# BG_IO_Schematic.net
KiCad netlist of a schematic drawn in Altium Designer
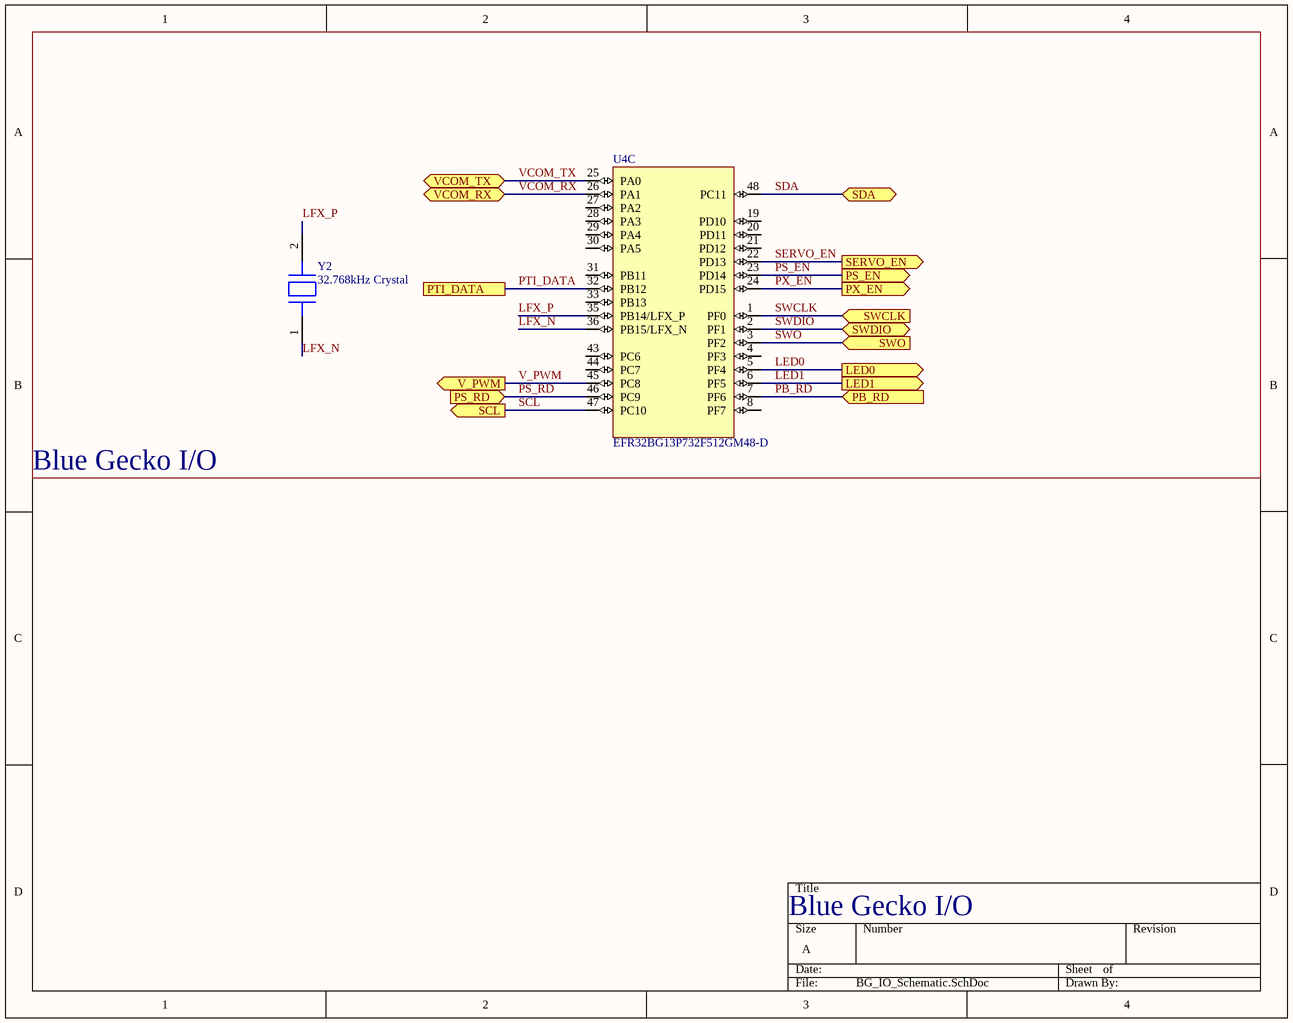
[diagram p0: BG_IO_Schematic.SchDoc]

(export (version "E")
  (design (tool "Eeschema 10.0.6"))
  (components
    (comp (ref "U4")
      (value "EFR32BG13P732F512GM48-D")
      (footprint "48-QFN_7x7")
      (description "Blue Gecko QFN48 2.4 G 19 dB BLE/Proprietary 512 kB 64 kB(RAM) 31GPIO")
      (fields (field (name "MANUFACTURER") "Silicon Labs"))
      (libsource (lib "PartsLib") (part "EFR32BG13P732F512GM48-D"))
    )
    (comp (ref "Y2")
      (value "32.768kHz Crystal")
      (footprint "DFN153P160X50-2N")
      (description "CRYSTAL 32.768KHZ 7PF SMD")
      (fields
        (field (name "MANUFACTURER") "Abracon")
        (field (name "MANUFACTURER PART NUMBER") "ABS05-32.768KHZ-7-T")
      )
      (libsource (lib "PartsLib") (part "ABS05-32.768KHZ-7-T"))
    )
  )
  (nets
    (net (code "1") (name "/LED0") (class "Default")
      (node (ref "U4") (pin "5") (pinfunction "PF4_5") (pintype "bidirectional"))
    )
    (net (code "2") (name "/LED1") (class "Default")
      (node (ref "U4") (pin "6") (pinfunction "PF5_6") (pintype "bidirectional"))
    )
    (net (code "3") (name "/LFX_N") (class "Default")
      (node (ref "U4") (pin "36") (pinfunction "PB15/LFX_N_36") (pintype "bidirectional"))
      (node (ref "Y2") (pin "1") (pinfunction "1_1") (pintype "passive"))
    )
    (net (code "4") (name "/LFX_P") (class "Default")
      (node (ref "U4") (pin "35") (pinfunction "PB14/LFX_P_35") (pintype "bidirectional"))
      (node (ref "Y2") (pin "2") (pinfunction "2_2") (pintype "passive"))
    )
    (net (code "5") (name "/PB_RD") (class "Default")
      (node (ref "U4") (pin "7") (pinfunction "PF6_7") (pintype "bidirectional"))
    )
    (net (code "6") (name "/PS_EN") (class "Default")
      (node (ref "U4") (pin "23") (pinfunction "PD14_23") (pintype "bidirectional"))
    )
    (net (code "7") (name "/PS_RD") (class "Default")
      (node (ref "U4") (pin "46") (pinfunction "PC9_46") (pintype "bidirectional"))
    )
    (net (code "8") (name "/PTI_DATA") (class "Default")
      (node (ref "U4") (pin "32") (pinfunction "PB12_32") (pintype "bidirectional"))
    )
    (net (code "9") (name "/PX_EN") (class "Default")
      (node (ref "U4") (pin "24") (pinfunction "PD15_24") (pintype "bidirectional"))
    )
    (net (code "10") (name "/SCL") (class "Default")
      (node (ref "U4") (pin "47") (pinfunction "PC10_47") (pintype "bidirectional"))
    )
    (net (code "11") (name "/SDA") (class "Default")
      (node (ref "U4") (pin "48") (pinfunction "PC11_48") (pintype "bidirectional"))
    )
    (net (code "12") (name "/SERVO_EN") (class "Default")
      (node (ref "U4") (pin "22") (pinfunction "PD13_22") (pintype "bidirectional"))
    )
    (net (code "13") (name "/SWCLK") (class "Default")
      (node (ref "U4") (pin "1") (pinfunction "PF0_1") (pintype "bidirectional"))
    )
    (net (code "14") (name "/SWDIO") (class "Default")
      (node (ref "U4") (pin "2") (pinfunction "PF1_2") (pintype "bidirectional"))
    )
    (net (code "15") (name "/SWO") (class "Default")
      (node (ref "U4") (pin "3") (pinfunction "PF2_3") (pintype "bidirectional"))
    )
    (net (code "16") (name "/VCOM_RX") (class "Default")
      (node (ref "U4") (pin "26") (pinfunction "PA1_26") (pintype "bidirectional"))
    )
    (net (code "17") (name "/VCOM_TX") (class "Default")
      (node (ref "U4") (pin "25") (pinfunction "PA0_25") (pintype "bidirectional"))
    )
    (net (code "18") (name "/V_PWM") (class "Default")
      (node (ref "U4") (pin "45") (pinfunction "PC8_45") (pintype "bidirectional"))
    )
    (net (code "19") (name "unconnected-(U4C-PA2-Pad27)") (class "Default")
      (node (ref "U4") (pin "27") (pinfunction "PA2_27") (pintype "bidirectional"))
    )
    (net (code "20") (name "unconnected-(U4C-PA3-Pad28)") (class "Default")
      (node (ref "U4") (pin "28") (pinfunction "PA3_28") (pintype "bidirectional"))
    )
    (net (code "21") (name "unconnected-(U4C-PA4-Pad29)") (class "Default")
      (node (ref "U4") (pin "29") (pinfunction "PA4_29") (pintype "bidirectional"))
    )
    (net (code "22") (name "unconnected-(U4C-PA5-Pad30)") (class "Default")
      (node (ref "U4") (pin "30") (pinfunction "PA5_30") (pintype "bidirectional"))
    )
    (net (code "23") (name "unconnected-(U4C-PB11-Pad31)") (class "Default")
      (node (ref "U4") (pin "31") (pinfunction "PB11_31") (pintype "bidirectional"))
    )
    (net (code "24") (name "unconnected-(U4C-PB13-Pad33)") (class "Default")
      (node (ref "U4") (pin "33") (pinfunction "PB13_33") (pintype "bidirectional"))
    )
    (net (code "25") (name "unconnected-(U4C-PC6-Pad43)") (class "Default")
      (node (ref "U4") (pin "43") (pinfunction "PC6_43") (pintype "bidirectional"))
    )
    (net (code "26") (name "unconnected-(U4C-PC7-Pad44)") (class "Default")
      (node (ref "U4") (pin "44") (pinfunction "PC7_44") (pintype "bidirectional"))
    )
    (net (code "27") (name "unconnected-(U4C-PD10-Pad19)") (class "Default")
      (node (ref "U4") (pin "19") (pinfunction "PD10_19") (pintype "bidirectional"))
    )
    (net (code "28") (name "unconnected-(U4C-PD11-Pad20)") (class "Default")
      (node (ref "U4") (pin "20") (pinfunction "PD11_20") (pintype "bidirectional"))
    )
    (net (code "29") (name "unconnected-(U4C-PD12-Pad21)") (class "Default")
      (node (ref "U4") (pin "21") (pinfunction "PD12_21") (pintype "bidirectional"))
    )
    (net (code "30") (name "unconnected-(U4C-PF3-Pad4)") (class "Default")
      (node (ref "U4") (pin "4") (pinfunction "PF3_4") (pintype "bidirectional"))
    )
    (net (code "31") (name "unconnected-(U4C-PF7-Pad8)") (class "Default")
      (node (ref "U4") (pin "8") (pinfunction "PF7_8") (pintype "bidirectional"))
    )
  )
)
